# signal_interface_opamp_buffer.net
KiCad netlist of a schematic drawn in EAGLE
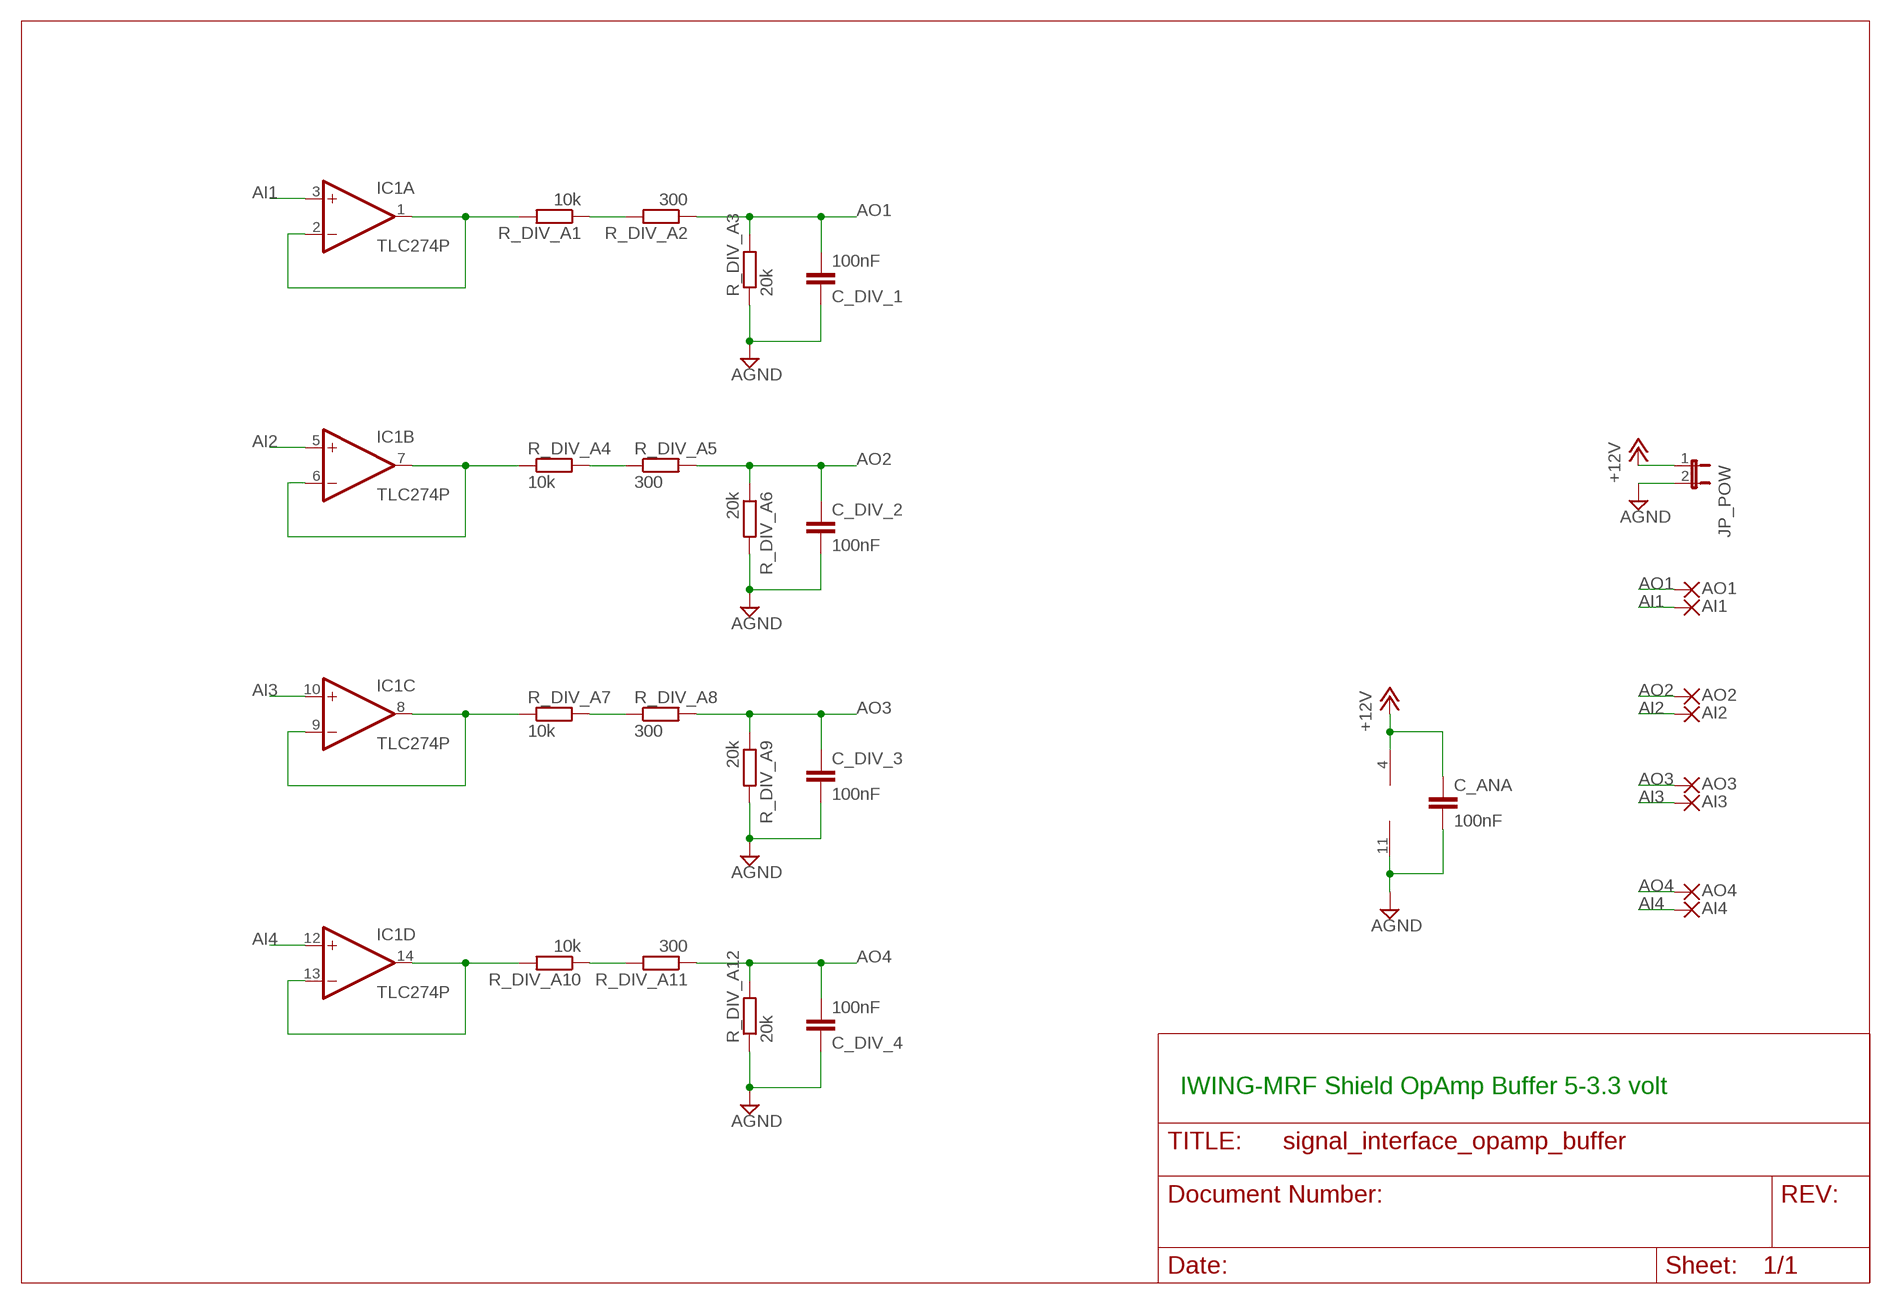
[diagram p0: schematic, sheet 1]

(export (version "E")
  (design (tool "Eeschema 10.0.6"))
  (components
    (comp (ref "AI1")
      (value "WIREPADSMD1,27-254")
      (footprint "eagle-import:SMD1,27-2,54")
      (libsource (lib "eagle-import") (part "WIREPADSMD1,27-254"))
    )
    (comp (ref "AI2")
      (value "WIREPADSMD1,27-254")
      (footprint "eagle-import:SMD1,27-2,54")
      (libsource (lib "eagle-import") (part "WIREPADSMD1,27-254"))
    )
    (comp (ref "AI3")
      (value "WIREPADSMD1,27-254")
      (footprint "eagle-import:SMD1,27-2,54")
      (libsource (lib "eagle-import") (part "WIREPADSMD1,27-254"))
    )
    (comp (ref "AI4")
      (value "WIREPADSMD1,27-254")
      (footprint "eagle-import:SMD1,27-2,54")
      (libsource (lib "eagle-import") (part "WIREPADSMD1,27-254"))
    )
    (comp (ref "AO1")
      (value "WIREPADSMD1,27-254")
      (footprint "eagle-import:SMD1,27-2,54")
      (libsource (lib "eagle-import") (part "WIREPADSMD1,27-254"))
    )
    (comp (ref "AO2")
      (value "WIREPADSMD1,27-254")
      (footprint "eagle-import:SMD1,27-2,54")
      (libsource (lib "eagle-import") (part "WIREPADSMD1,27-254"))
    )
    (comp (ref "AO3")
      (value "WIREPADSMD1,27-254")
      (footprint "eagle-import:SMD1,27-2,54")
      (libsource (lib "eagle-import") (part "WIREPADSMD1,27-254"))
    )
    (comp (ref "AO4")
      (value "WIREPADSMD1,27-254")
      (footprint "eagle-import:SMD1,27-2,54")
      (libsource (lib "eagle-import") (part "WIREPADSMD1,27-254"))
    )
    (comp (ref "C_ANA")
      (value "100nF")
      (footprint "eagle-import:RCL_C050-025X075")
      (libsource (lib "eagle-import") (part "RCL_C-EU050-025X075"))
    )
    (comp (ref "C_DIV_1")
      (value "100nF")
      (footprint "eagle-import:RCL_C050-025X075")
      (libsource (lib "eagle-import") (part "RCL_C-EU050-025X075"))
    )
    (comp (ref "C_DIV_2")
      (value "100nF")
      (footprint "eagle-import:RCL_C050-025X075")
      (libsource (lib "eagle-import") (part "RCL_C-EU050-025X075"))
    )
    (comp (ref "C_DIV_3")
      (value "100nF")
      (footprint "eagle-import:RCL_C050-025X075")
      (libsource (lib "eagle-import") (part "RCL_C-EU050-025X075"))
    )
    (comp (ref "C_DIV_4")
      (value "100nF")
      (footprint "eagle-import:RCL_C050-025X075")
      (libsource (lib "eagle-import") (part "RCL_C-EU050-025X075"))
    )
    (comp (ref "IC1")
      (value "TLC274P")
      (footprint "eagle-import:DIL14")
      (libsource (lib "eagle-import") (part "TLC274P"))
    )
    (comp (ref "JP_POW")
      (value "JUMPER-2PTH")
      (footprint "eagle-import:1X02")
      (libsource (lib "eagle-import") (part "JUMPER-2PTH"))
    )
    (comp (ref "R_DIV_A1")
      (value "10k")
      (footprint "eagle-import:0204V")
      (libsource (lib "eagle-import") (part "R-EU_0204/2V"))
    )
    (comp (ref "R_DIV_A2")
      (value "300")
      (footprint "eagle-import:0204V")
      (libsource (lib "eagle-import") (part "R-EU_0204/2V"))
    )
    (comp (ref "R_DIV_A3")
      (value "20k")
      (footprint "eagle-import:0204V")
      (libsource (lib "eagle-import") (part "R-EU_0204/2V"))
    )
    (comp (ref "R_DIV_A4")
      (value "10k")
      (footprint "eagle-import:0204V")
      (libsource (lib "eagle-import") (part "R-EU_0204/2V"))
    )
    (comp (ref "R_DIV_A5")
      (value "300")
      (footprint "eagle-import:0204V")
      (libsource (lib "eagle-import") (part "R-EU_0204/2V"))
    )
    (comp (ref "R_DIV_A6")
      (value "20k")
      (footprint "eagle-import:0204V")
      (libsource (lib "eagle-import") (part "R-EU_0204/2V"))
    )
    (comp (ref "R_DIV_A7")
      (value "10k")
      (footprint "eagle-import:0204V")
      (libsource (lib "eagle-import") (part "R-EU_0204/2V"))
    )
    (comp (ref "R_DIV_A8")
      (value "300")
      (footprint "eagle-import:0204V")
      (libsource (lib "eagle-import") (part "R-EU_0204/2V"))
    )
    (comp (ref "R_DIV_A9")
      (value "20k")
      (footprint "eagle-import:0204V")
      (libsource (lib "eagle-import") (part "R-EU_0204/2V"))
    )
    (comp (ref "R_DIV_A10")
      (value "10k")
      (footprint "eagle-import:0204V")
      (libsource (lib "eagle-import") (part "R-EU_0204/2V"))
    )
    (comp (ref "R_DIV_A11")
      (value "300")
      (footprint "eagle-import:0204V")
      (libsource (lib "eagle-import") (part "R-EU_0204/2V"))
    )
    (comp (ref "R_DIV_A12")
      (value "20k")
      (footprint "eagle-import:0204V")
      (libsource (lib "eagle-import") (part "R-EU_0204/2V"))
    )
  )
  (nets
    (net (code "1") (name "+12V") (class "Default")
      (node (ref "C_ANA") (pin "1") (pinfunction "1_1") (pintype "passive"))
      (node (ref "IC1") (pin "4") (pinfunction "V+_4") (pintype "power_in"))
      (node (ref "JP_POW") (pin "1") (pinfunction "1_1") (pintype "passive"))
    )
    (net (code "2") (name "/AI1") (class "Default")
      (node (ref "AI1") (pin "1") (pinfunction "P_1") (pintype "passive"))
      (node (ref "IC1") (pin "3") (pinfunction "+IN_3") (pintype "input"))
    )
    (net (code "3") (name "/AI2") (class "Default")
      (node (ref "AI2") (pin "1") (pinfunction "P_1") (pintype "passive"))
      (node (ref "IC1") (pin "5") (pinfunction "+IN_5") (pintype "input"))
    )
    (net (code "4") (name "/AI3") (class "Default")
      (node (ref "AI3") (pin "1") (pinfunction "P_1") (pintype "passive"))
      (node (ref "IC1") (pin "10") (pinfunction "+IN_10") (pintype "input"))
    )
    (net (code "5") (name "/AI4") (class "Default")
      (node (ref "AI4") (pin "1") (pinfunction "P_1") (pintype "passive"))
      (node (ref "IC1") (pin "12") (pinfunction "+IN_12") (pintype "input"))
    )
    (net (code "6") (name "/AO1") (class "Default")
      (node (ref "AO1") (pin "1") (pinfunction "P_1") (pintype "passive"))
      (node (ref "C_DIV_1") (pin "2") (pinfunction "2_2") (pintype "passive"))
      (node (ref "R_DIV_A2") (pin "1") (pinfunction "1_1") (pintype "passive"))
      (node (ref "R_DIV_A3") (pin "2") (pinfunction "2_2") (pintype "passive"))
    )
    (net (code "7") (name "/AO2") (class "Default")
      (node (ref "AO2") (pin "1") (pinfunction "P_1") (pintype "passive"))
      (node (ref "C_DIV_2") (pin "1") (pinfunction "1_1") (pintype "passive"))
      (node (ref "R_DIV_A5") (pin "2") (pinfunction "2_2") (pintype "passive"))
      (node (ref "R_DIV_A6") (pin "1") (pinfunction "1_1") (pintype "passive"))
    )
    (net (code "8") (name "/AO3") (class "Default")
      (node (ref "AO3") (pin "1") (pinfunction "P_1") (pintype "passive"))
      (node (ref "C_DIV_3") (pin "1") (pinfunction "1_1") (pintype "passive"))
      (node (ref "R_DIV_A8") (pin "2") (pinfunction "2_2") (pintype "passive"))
      (node (ref "R_DIV_A9") (pin "1") (pinfunction "1_1") (pintype "passive"))
    )
    (net (code "9") (name "/AO4") (class "Default")
      (node (ref "AO4") (pin "1") (pinfunction "P_1") (pintype "passive"))
      (node (ref "C_DIV_4") (pin "2") (pinfunction "2_2") (pintype "passive"))
      (node (ref "R_DIV_A11") (pin "1") (pinfunction "1_1") (pintype "passive"))
      (node (ref "R_DIV_A12") (pin "2") (pinfunction "2_2") (pintype "passive"))
    )
    (net (code "10") (name "AGND") (class "Default")
      (node (ref "C_ANA") (pin "2") (pinfunction "2_2") (pintype "passive"))
      (node (ref "C_DIV_1") (pin "1") (pinfunction "1_1") (pintype "passive"))
      (node (ref "C_DIV_2") (pin "2") (pinfunction "2_2") (pintype "passive"))
      (node (ref "C_DIV_3") (pin "2") (pinfunction "2_2") (pintype "passive"))
      (node (ref "C_DIV_4") (pin "1") (pinfunction "1_1") (pintype "passive"))
      (node (ref "IC1") (pin "11") (pinfunction "V-_11") (pintype "power_in"))
      (node (ref "JP_POW") (pin "2") (pinfunction "2_2") (pintype "passive"))
      (node (ref "R_DIV_A12") (pin "1") (pinfunction "1_1") (pintype "passive"))
      (node (ref "R_DIV_A3") (pin "1") (pinfunction "1_1") (pintype "passive"))
      (node (ref "R_DIV_A6") (pin "2") (pinfunction "2_2") (pintype "passive"))
      (node (ref "R_DIV_A9") (pin "2") (pinfunction "2_2") (pintype "passive"))
    )
    (net (code "11") (name "Net-(IC1A--IN)") (class "Default")
      (node (ref "IC1") (pin "1") (pinfunction "OUT_1") (pintype "output"))
      (node (ref "IC1") (pin "2") (pinfunction "-IN_2") (pintype "input"))
      (node (ref "R_DIV_A1") (pin "2") (pinfunction "2_2") (pintype "passive"))
    )
    (net (code "12") (name "Net-(IC1B--IN)") (class "Default")
      (node (ref "IC1") (pin "6") (pinfunction "-IN_6") (pintype "input"))
      (node (ref "IC1") (pin "7") (pinfunction "OUT_7") (pintype "output"))
      (node (ref "R_DIV_A4") (pin "1") (pinfunction "1_1") (pintype "passive"))
    )
    (net (code "13") (name "Net-(IC1C--IN)") (class "Default")
      (node (ref "IC1") (pin "8") (pinfunction "OUT_8") (pintype "output"))
      (node (ref "IC1") (pin "9") (pinfunction "-IN_9") (pintype "input"))
      (node (ref "R_DIV_A7") (pin "1") (pinfunction "1_1") (pintype "passive"))
    )
    (net (code "14") (name "Net-(IC1D--IN)") (class "Default")
      (node (ref "IC1") (pin "13") (pinfunction "-IN_13") (pintype "input"))
      (node (ref "IC1") (pin "14") (pinfunction "OUT_14") (pintype "output"))
      (node (ref "R_DIV_A10") (pin "2") (pinfunction "2_2") (pintype "passive"))
    )
    (net (code "15") (name "Net-(R_DIV_A1-Pad1)") (class "Default")
      (node (ref "R_DIV_A1") (pin "1") (pinfunction "1_1") (pintype "passive"))
      (node (ref "R_DIV_A2") (pin "2") (pinfunction "2_2") (pintype "passive"))
    )
    (net (code "16") (name "Net-(R_DIV_A4-Pad2)") (class "Default")
      (node (ref "R_DIV_A4") (pin "2") (pinfunction "2_2") (pintype "passive"))
      (node (ref "R_DIV_A5") (pin "1") (pinfunction "1_1") (pintype "passive"))
    )
    (net (code "17") (name "Net-(R_DIV_A7-Pad2)") (class "Default")
      (node (ref "R_DIV_A7") (pin "2") (pinfunction "2_2") (pintype "passive"))
      (node (ref "R_DIV_A8") (pin "1") (pinfunction "1_1") (pintype "passive"))
    )
    (net (code "18") (name "Net-(R_DIV_A10-Pad1)") (class "Default")
      (node (ref "R_DIV_A10") (pin "1") (pinfunction "1_1") (pintype "passive"))
      (node (ref "R_DIV_A11") (pin "2") (pinfunction "2_2") (pintype "passive"))
    )
  )
)
